# 2016_CanSat_payload_main_final.net
KiCad netlist of a schematic drawn in EAGLE
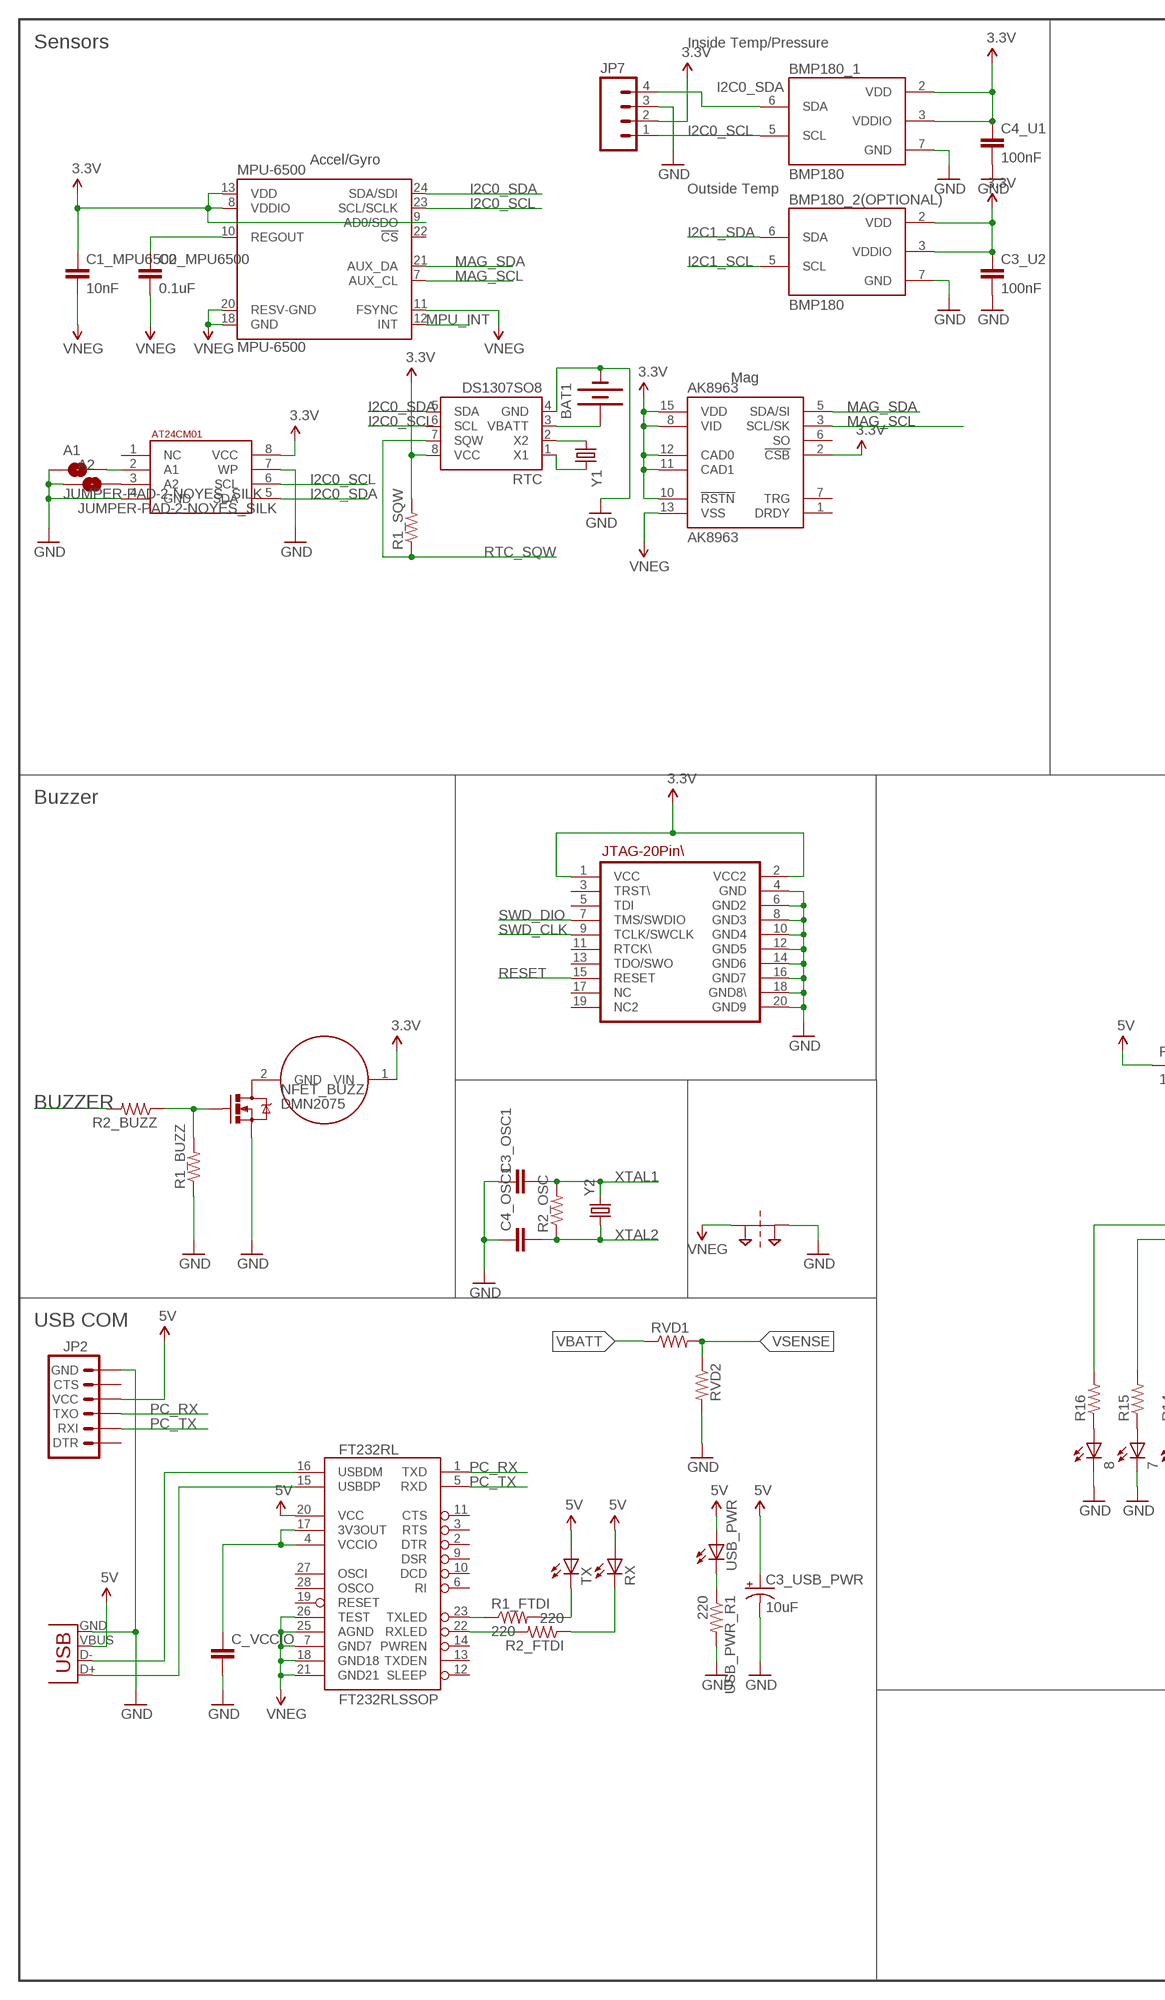
[diagram p0: schematic, sheet 1, part 1 of 2]
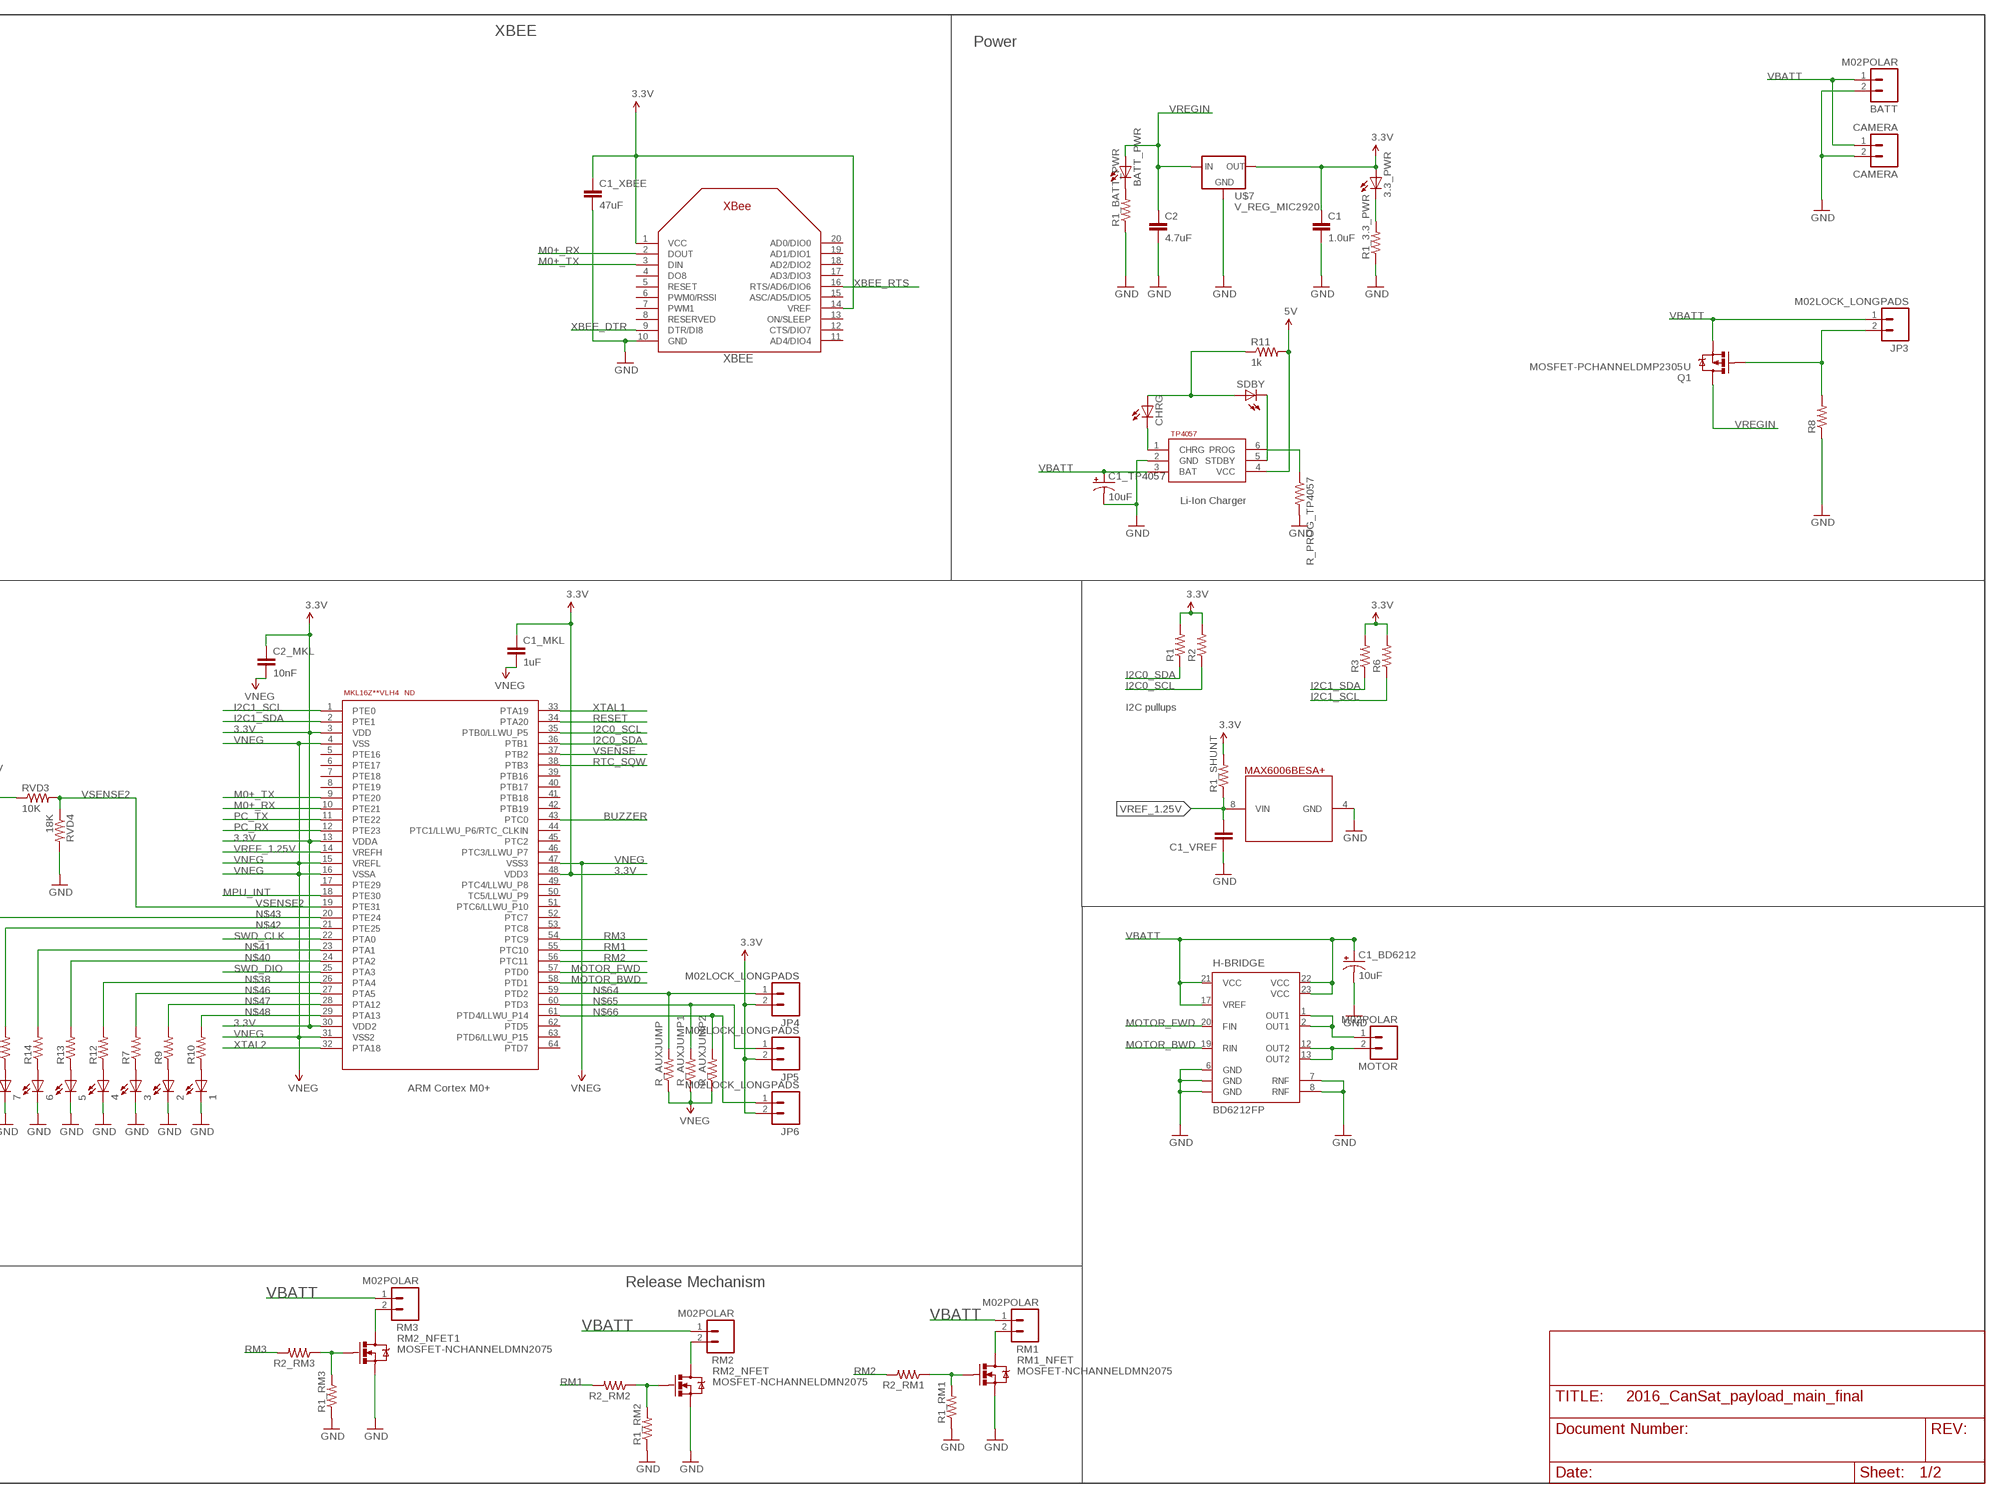
[diagram p1: schematic, sheet 1, part 2 of 2]

(export (version "E")
  (design (tool "Eeschema 10.0.6"))
  (components
    (comp (ref "1")
      (value "LEDCHIP-LED0603")
      (footprint "eagle-import:CHIP-LED0603")
      (libsource (lib "eagle-import") (part "LEDCHIP-LED0603"))
    )
    (comp (ref "2")
      (value "LEDCHIP-LED0603")
      (footprint "eagle-import:CHIP-LED0603")
      (libsource (lib "eagle-import") (part "LEDCHIP-LED0603"))
    )
    (comp (ref "3")
      (value "LEDCHIP-LED0603")
      (footprint "eagle-import:CHIP-LED0603")
      (libsource (lib "eagle-import") (part "LEDCHIP-LED0603"))
    )
    (comp (ref "3.3_PWR")
      (value "LEDCHIP-LED0603")
      (footprint "eagle-import:CHIP-LED0603")
      (libsource (lib "eagle-import") (part "LEDCHIP-LED0603"))
    )
    (comp (ref "4")
      (value "LEDCHIP-LED0603")
      (footprint "eagle-import:CHIP-LED0603")
      (libsource (lib "eagle-import") (part "LEDCHIP-LED0603"))
    )
    (comp (ref "5")
      (value "LEDCHIP-LED0603")
      (footprint "eagle-import:CHIP-LED0603")
      (libsource (lib "eagle-import") (part "LEDCHIP-LED0603"))
    )
    (comp (ref "6")
      (value "LEDCHIP-LED0603")
      (footprint "eagle-import:CHIP-LED0603")
      (libsource (lib "eagle-import") (part "LEDCHIP-LED0603"))
    )
    (comp (ref "7")
      (value "LEDCHIP-LED0603")
      (footprint "eagle-import:CHIP-LED0603")
      (libsource (lib "eagle-import") (part "LEDCHIP-LED0603"))
    )
    (comp (ref "8")
      (value "LEDCHIP-LED0603")
      (footprint "eagle-import:CHIP-LED0603")
      (libsource (lib "eagle-import") (part "LEDCHIP-LED0603"))
    )
    (comp (ref "A1")
      (value "JUMPER-PAD-2-NOYES_SILK")
      (footprint "eagle-import:PAD-JUMPER-2-NO_YES_SILK")
      (libsource (lib "eagle-import") (part "JUMPER-PAD-2-NOYES_SILK"))
    )
    (comp (ref "A2")
      (value "JUMPER-PAD-2-NOYES_SILK")
      (footprint "eagle-import:PAD-JUMPER-2-NO_YES_SILK")
      (libsource (lib "eagle-import") (part "JUMPER-PAD-2-NOYES_SILK"))
    )
    (comp (ref "AK8963")
      (value "AK8963")
      (footprint "eagle-import:QFN16-HS")
      (libsource (lib "eagle-import") (part "AK8963"))
    )
    (comp (ref "BAT1")
      (value "BATTERY12MM")
      (footprint "eagle-import:BATTCON_12MM")
      (libsource (lib "eagle-import") (part "BATTERY12MM"))
    )
    (comp (ref "BATT")
      (value "M02POLAR")
      (footprint "eagle-import:MOLEX-1X2")
      (libsource (lib "eagle-import") (part "M02POLAR"))
    )
    (comp (ref "BATT_PWR")
      (value "LEDCHIP-LED0603")
      (footprint "eagle-import:CHIP-LED0603")
      (libsource (lib "eagle-import") (part "LEDCHIP-LED0603"))
    )
    (comp (ref "BMP180_1")
      (value "BMP180")
      (footprint "eagle-import:BMP180")
      (libsource (lib "eagle-import") (part "BMP180"))
    )
    (comp (ref "BMP180_2(OPTIONAL)")
      (value "BMP180")
      (footprint "eagle-import:BMP180")
      (libsource (lib "eagle-import") (part "BMP180"))
    )
    (comp (ref "C1")
      (value "1.0uF")
      (footprint "eagle-import:0603-CAP")
      (libsource (lib "eagle-import") (part "1.0UF-16V-10%(0603)"))
    )
    (comp (ref "C1_BD6212")
      (value "10uF")
      (footprint "eagle-import:EIA3216")
      (libsource (lib "eagle-import") (part "10UF-16V-10%(TANT)"))
    )
    (comp (ref "C1_MKL")
      (value "1uF")
      (footprint "eagle-import:0603-CAP")
      (libsource (lib "eagle-import") (part "CAP0603-CAP"))
    )
    (comp (ref "C1_MPU6500")
      (value "10nF")
      (footprint "eagle-import:0603-CAP")
      (libsource (lib "eagle-import") (part "CAP0603-CAP"))
    )
    (comp (ref "C1_TP4057")
      (value "10uF")
      (footprint "eagle-import:EIA3216")
      (libsource (lib "eagle-import") (part "10UF-16V-10%(TANT)"))
    )
    (comp (ref "C1_VREF")
      (value "CAP0603-CAP")
      (footprint "eagle-import:0603-CAP")
      (libsource (lib "eagle-import") (part "SparkFun-Passives_CAP0603-CAP"))
    )
    (comp (ref "C1_XBEE")
      (value "47uF")
      (footprint "eagle-import:0603-CAP")
      (libsource (lib "eagle-import") (part "CAP0603-CAP"))
    )
    (comp (ref "C2")
      (value "4.7uF")
      (footprint "eagle-import:0603-CAP")
      (libsource (lib "eagle-import") (part "4.7UF-6.3V-10%(0603)0603"))
    )
    (comp (ref "C2_MKL")
      (value "10nF")
      (footprint "eagle-import:0603-CAP")
      (libsource (lib "eagle-import") (part "CAP0603-CAP"))
    )
    (comp (ref "C2_MPU6500")
      (value "0.1uF")
      (footprint "eagle-import:0603-CAP")
      (libsource (lib "eagle-import") (part "CAP0603-CAP"))
    )
    (comp (ref "C3_OSC1")
      (value "CAP0603-CAP")
      (footprint "eagle-import:0603-CAP")
      (libsource (lib "eagle-import") (part "SparkFun-Passives_CAP0603-CAP"))
    )
    (comp (ref "C3_U2")
      (value "100nF")
      (footprint "eagle-import:0603-CAP")
      (libsource (lib "eagle-import") (part "CAP0603-CAP"))
    )
    (comp (ref "C3_USB_PWR")
      (value "10uF")
      (footprint "eagle-import:EIA3216")
      (libsource (lib "eagle-import") (part "10UF-16V-10%(TANT)"))
    )
    (comp (ref "C4_OSC1")
      (value "CAP0603-CAP")
      (footprint "eagle-import:0603-CAP")
      (libsource (lib "eagle-import") (part "SparkFun-Passives_CAP0603-CAP"))
    )
    (comp (ref "C4_U1")
      (value "100nF")
      (footprint "eagle-import:0603-CAP")
      (libsource (lib "eagle-import") (part "CAP0603-CAP"))
    )
    (comp (ref "CAMERA")
      (value "CAMERA")
      (footprint "eagle-import:MOLEX-1X2")
      (libsource (lib "eagle-import") (part "M02POLAR"))
    )
    (comp (ref "CHRG")
      (value "LEDCHIPLED_0603")
      (footprint "eagle-import:CHIPLED_0603")
      (libsource (lib "eagle-import") (part "LEDCHIPLED_0603"))
    )
    (comp (ref "C_VCCIO")
      (value "CAP0603-CAP")
      (footprint "eagle-import:0603-CAP")
      (libsource (lib "eagle-import") (part "CAP0603-CAP"))
    )
    (comp (ref "FT232RL")
      (value "FT232RLSSOP")
      (footprint "eagle-import:SSOP28DB")
      (libsource (lib "eagle-import") (part "FT232RLSSOP"))
    )
    (comp (ref "H-BRIDGE")
      (value "BD6212FP")
      (footprint "eagle-import:HSOP25")
      (libsource (lib "eagle-import") (part "BD6212FP"))
    )
    (comp (ref "JP1")
      (value "USBOLD")
      (footprint "eagle-import:USB-MINIB-OLD")
      (libsource (lib "eagle-import") (part "USBOLD"))
    )
    (comp (ref "JP2")
      (value "ARDUINO_SERIAL_PROGRAMLONGPADS")
      (footprint "eagle-import:1X06_LONGPADS")
      (libsource (lib "eagle-import") (part "ARDUINO_SERIAL_PROGRAMLONGPADS"))
    )
    (comp (ref "JP3")
      (value "M02LOCK_LONGPADS")
      (footprint "eagle-import:1X02_LOCK_LONGPADS")
      (libsource (lib "eagle-import") (part "M02LOCK_LONGPADS"))
    )
    (comp (ref "JP4")
      (value "M02LOCK_LONGPADS")
      (footprint "eagle-import:1X02_LOCK_LONGPADS")
      (libsource (lib "eagle-import") (part "M02LOCK_LONGPADS"))
    )
    (comp (ref "JP5")
      (value "M02LOCK_LONGPADS")
      (footprint "eagle-import:1X02_LOCK_LONGPADS")
      (libsource (lib "eagle-import") (part "M02LOCK_LONGPADS"))
    )
    (comp (ref "JP6")
      (value "M02LOCK_LONGPADS")
      (footprint "eagle-import:1X02_LOCK_LONGPADS")
      (libsource (lib "eagle-import") (part "M02LOCK_LONGPADS"))
    )
    (comp (ref "JP7")
      (value "M04POLAR")
      (footprint "eagle-import:MOLEX-1X4")
      (libsource (lib "eagle-import") (part "M04POLAR"))
    )
    (comp (ref "JTAG")
      (value "JTAG_20PIN")
      (footprint "eagle-import:2X10")
      (libsource (lib "eagle-import") (part "JTAG_20PIN"))
    )
    (comp (ref "MKL16")
      (value "MKL16ZVLH4-ND")
      (footprint "eagle-import:TQFP64")
      (libsource (lib "eagle-import") (part "MKL16ZVLH4-ND"))
    )
    (comp (ref "MOTOR")
      (value "M02POLAR")
      (footprint "eagle-import:MOLEX-1X2")
      (libsource (lib "eagle-import") (part "M02POLAR"))
    )
    (comp (ref "MPU-6500")
      (value "MPU-6500")
      (footprint "eagle-import:QFN-24")
      (libsource (lib "eagle-import") (part "MPU-6500"))
    )
    (comp (ref "NFET_BUZZ")
      (value "DMN2075")
      (footprint "eagle-import:SOT23")
      (libsource (lib "eagle-import") (part "MOSFET-NCHANNELDMN2075"))
    )
    (comp (ref "PT1")
      (value "2PT_GND_TIE")
      (footprint "eagle-import:2PT_GND_TIE")
      (libsource (lib "eagle-import") (part "2PT_GND_TIE"))
    )
    (comp (ref "Q1")
      (value "MOSFET-PCHANNELDMP2305U")
      (footprint "eagle-import:SOT23-3")
      (libsource (lib "eagle-import") (part "MOSFET-PCHANNELDMP2305U"))
    )
    (comp (ref "R1")
      (value "RESISTOR0603-RES")
      (footprint "eagle-import:0603-RES")
      (libsource (lib "eagle-import") (part "RESISTOR0603-RES"))
    )
    (comp (ref "R1_3.3_PWR")
      (value "RESISTOR0603")
      (footprint "eagle-import:0603-RES")
      (libsource (lib "eagle-import") (part "RESISTOR0603"))
    )
    (comp (ref "R1_BATT_PWR")
      (value "RESISTOR0603")
      (footprint "eagle-import:0603-RES")
      (libsource (lib "eagle-import") (part "RESISTOR0603"))
    )
    (comp (ref "R1_BUZZ")
      (value "RESISTOR0805-RES")
      (footprint "eagle-import:0805")
      (libsource (lib "eagle-import") (part "SparkFun-Resistors_RESISTOR0805-RES"))
    )
    (comp (ref "R1_FTDI")
      (value "220")
      (footprint "eagle-import:0603-RES")
      (libsource (lib "eagle-import") (part "RESISTOR0603-RES"))
    )
    (comp (ref "R1_RM1")
      (value "RESISTOR0805-RES")
      (footprint "eagle-import:0805")
      (libsource (lib "eagle-import") (part "SparkFun-Resistors_RESISTOR0805-RES"))
    )
    (comp (ref "R1_RM2")
      (value "RESISTOR0805-RES")
      (footprint "eagle-import:0805")
      (libsource (lib "eagle-import") (part "SparkFun-Resistors_RESISTOR0805-RES"))
    )
    (comp (ref "R1_RM3")
      (value "RESISTOR0805-RES")
      (footprint "eagle-import:0805")
      (libsource (lib "eagle-import") (part "SparkFun-Resistors_RESISTOR0805-RES"))
    )
    (comp (ref "R1_SHUNT")
      (value "RESISTOR0805-RES")
      (footprint "eagle-import:0805")
      (libsource (lib "eagle-import") (part "SparkFun-Resistors_RESISTOR0805-RES"))
    )
    (comp (ref "R1_SQW")
      (value "RESISTOR0603-RES")
      (footprint "eagle-import:0603-RES")
      (libsource (lib "eagle-import") (part "RESISTOR0603-RES"))
    )
    (comp (ref "R2")
      (value "RESISTOR0603-RES")
      (footprint "eagle-import:0603-RES")
      (libsource (lib "eagle-import") (part "RESISTOR0603-RES"))
    )
    (comp (ref "R2_BUZZ")
      (value "RESISTOR0805-RES")
      (footprint "eagle-import:0805")
      (libsource (lib "eagle-import") (part "SparkFun-Resistors_RESISTOR0805-RES"))
    )
    (comp (ref "R2_FTDI")
      (value "220")
      (footprint "eagle-import:0603-RES")
      (libsource (lib "eagle-import") (part "RESISTOR0603-RES"))
    )
    (comp (ref "R2_OSC")
      (value "RESISTOR0805-RES")
      (footprint "eagle-import:0805")
      (libsource (lib "eagle-import") (part "SparkFun-Resistors_RESISTOR0805-RES"))
    )
    (comp (ref "R2_RM1")
      (value "RESISTOR0805-RES")
      (footprint "eagle-import:0805")
      (libsource (lib "eagle-import") (part "SparkFun-Resistors_RESISTOR0805-RES"))
    )
    (comp (ref "R2_RM2")
      (value "RESISTOR0805-RES")
      (footprint "eagle-import:0805")
      (libsource (lib "eagle-import") (part "SparkFun-Resistors_RESISTOR0805-RES"))
    )
    (comp (ref "R2_RM3")
      (value "RESISTOR0805-RES")
      (footprint "eagle-import:0805")
      (libsource (lib "eagle-import") (part "SparkFun-Resistors_RESISTOR0805-RES"))
    )
    (comp (ref "R3")
      (value "RESISTOR0603-RES")
      (footprint "eagle-import:0603-RES")
      (libsource (lib "eagle-import") (part "RESISTOR0603-RES"))
    )
    (comp (ref "R6")
      (value "RESISTOR0603-RES")
      (footprint "eagle-import:0603-RES")
      (libsource (lib "eagle-import") (part "RESISTOR0603-RES"))
    )
    (comp (ref "R7")
      (value "RESISTOR0603-RES")
      (footprint "eagle-import:0603-RES")
      (libsource (lib "eagle-import") (part "RESISTOR0603-RES"))
    )
    (comp (ref "R8")
      (value "RESISTOR0603")
      (footprint "eagle-import:0603-RES")
      (libsource (lib "eagle-import") (part "RESISTOR0603"))
    )
    (comp (ref "R9")
      (value "RESISTOR0603-RES")
      (footprint "eagle-import:0603-RES")
      (libsource (lib "eagle-import") (part "RESISTOR0603-RES"))
    )
    (comp (ref "R10")
      (value "RESISTOR0603-RES")
      (footprint "eagle-import:0603-RES")
      (libsource (lib "eagle-import") (part "RESISTOR0603-RES"))
    )
    (comp (ref "R11")
      (value "1k")
      (footprint "eagle-import:0603-RES")
      (libsource (lib "eagle-import") (part "RESISTOR0603"))
    )
    (comp (ref "R12")
      (value "RESISTOR0603-RES")
      (footprint "eagle-import:0603-RES")
      (libsource (lib "eagle-import") (part "RESISTOR0603-RES"))
    )
    (comp (ref "R13")
      (value "RESISTOR0603-RES")
      (footprint "eagle-import:0603-RES")
      (libsource (lib "eagle-import") (part "RESISTOR0603-RES"))
    )
    (comp (ref "R14")
      (value "RESISTOR0603-RES")
      (footprint "eagle-import:0603-RES")
      (libsource (lib "eagle-import") (part "RESISTOR0603-RES"))
    )
    (comp (ref "R15")
      (value "RESISTOR0603-RES")
      (footprint "eagle-import:0603-RES")
      (libsource (lib "eagle-import") (part "RESISTOR0603-RES"))
    )
    (comp (ref "R16")
      (value "RESISTOR0603-RES")
      (footprint "eagle-import:0603-RES")
      (libsource (lib "eagle-import") (part "RESISTOR0603-RES"))
    )
    (comp (ref "RM1")
      (value "M02POLAR")
      (footprint "eagle-import:MOLEX-1X2")
      (libsource (lib "eagle-import") (part "M02POLAR"))
    )
    (comp (ref "RM1_NFET")
      (value "MOSFET-NCHANNELDMN2075")
      (footprint "eagle-import:SOT23")
      (libsource (lib "eagle-import") (part "MOSFET-NCHANNELDMN2075"))
    )
    (comp (ref "RM2")
      (value "M02POLAR")
      (footprint "eagle-import:MOLEX-1X2")
      (libsource (lib "eagle-import") (part "M02POLAR"))
    )
    (comp (ref "RM2_NFET")
      (value "MOSFET-NCHANNELDMN2075")
      (footprint "eagle-import:SOT23")
      (libsource (lib "eagle-import") (part "MOSFET-NCHANNELDMN2075"))
    )
    (comp (ref "RM2_NFET1")
      (value "MOSFET-NCHANNELDMN2075")
      (footprint "eagle-import:SOT23")
      (libsource (lib "eagle-import") (part "MOSFET-NCHANNELDMN2075"))
    )
    (comp (ref "RM3")
      (value "M02POLAR")
      (footprint "eagle-import:MOLEX-1X2")
      (libsource (lib "eagle-import") (part "M02POLAR"))
    )
    (comp (ref "RTC")
      (value "DS1307SO8")
      (footprint "eagle-import:SO08")
      (libsource (lib "eagle-import") (part "DS1307SO8"))
    )
    (comp (ref "RVD1")
      (value "RESISTOR0805-RES")
      (footprint "eagle-import:0805")
      (libsource (lib "eagle-import") (part "SparkFun-Resistors_RESISTOR0805-RES"))
    )
    (comp (ref "RVD2")
      (value "RESISTOR0805-RES")
      (footprint "eagle-import:0805")
      (libsource (lib "eagle-import") (part "SparkFun-Resistors_RESISTOR0805-RES"))
    )
    (comp (ref "RVD3")
      (value "10K")
      (footprint "eagle-import:0805")
      (libsource (lib "eagle-import") (part "SparkFun-Resistors_RESISTOR0805-RES"))
    )
    (comp (ref "RVD4")
      (value "18K")
      (footprint "eagle-import:0805")
      (libsource (lib "eagle-import") (part "SparkFun-Resistors_RESISTOR0805-RES"))
    )
    (comp (ref "RX")
      (value "LEDCHIPLED_0603")
      (footprint "eagle-import:CHIPLED_0603")
      (libsource (lib "eagle-import") (part "LEDCHIPLED_0603"))
    )
    (comp (ref "R_AUXJUMP")
      (value "RESISTOR0805-RES")
      (footprint "eagle-import:0805")
      (libsource (lib "eagle-import") (part "SparkFun-Resistors_RESISTOR0805-RES"))
    )
    (comp (ref "R_AUXJUMP1")
      (value "RESISTOR0805-RES")
      (footprint "eagle-import:0805")
      (libsource (lib "eagle-import") (part "SparkFun-Resistors_RESISTOR0805-RES"))
    )
    (comp (ref "R_AUXJUMP2")
      (value "RESISTOR0805-RES")
      (footprint "eagle-import:0805")
      (libsource (lib "eagle-import") (part "SparkFun-Resistors_RESISTOR0805-RES"))
    )
    (comp (ref "R_PROG_TP4057")
      (value "RESISTOR0603")
      (footprint "eagle-import:0603-RES")
      (libsource (lib "eagle-import") (part "RESISTOR0603"))
    )
    (comp (ref "SDBY")
      (value "LEDCHIPLED_0603")
      (footprint "eagle-import:CHIPLED_0603")
      (libsource (lib "eagle-import") (part "LEDCHIPLED_0603"))
    )
    (comp (ref "TX")
      (value "LEDCHIPLED_0603")
      (footprint "eagle-import:CHIPLED_0603")
      (libsource (lib "eagle-import") (part "LEDCHIPLED_0603"))
    )
    (comp (ref "U$2")
      (value "AT24CM01")
      (footprint "eagle-import:SO08")
      (libsource (lib "eagle-import") (part "AT24CM01"))
    )
    (comp (ref "U$3")
      (value "TP4057")
      (footprint "eagle-import:SOT23-6")
      (libsource (lib "eagle-import") (part "TP4057"))
    )
    (comp (ref "U$4")
      (value "AI-1027-TWT-3V-R_BUZZER")
      (footprint "eagle-import:AI-1027-TWT-3V-R_BUZZER")
      (libsource (lib "eagle-import") (part "AI-1027-TWT-3V-R_BUZZER"))
    )
    (comp (ref "U$5")
      (value "MAX6006BESA+")
      (footprint "eagle-import:SO08")
      (libsource (lib "eagle-import") (part "MAX6006BESA+"))
    )
    (comp (ref "U$7")
      (value "V_REG_MIC2920")
      (footprint "eagle-import:SOT223")
      (libsource (lib "eagle-import") (part "V_REG_MIC2920"))
    )
    (comp (ref "USB_PWR")
      (value "LEDCHIPLED_0603")
      (footprint "eagle-import:CHIPLED_0603")
      (libsource (lib "eagle-import") (part "LEDCHIPLED_0603"))
    )
    (comp (ref "USB_PWR_R1")
      (value "220")
      (footprint "eagle-import:0603-RES")
      (libsource (lib "eagle-import") (part "RESISTOR0603-RES"))
    )
    (comp (ref "XBEE")
      (value "XBEE")
      (footprint "eagle-import:XBEE")
      (libsource (lib "eagle-import") (part "XBEE"))
    )
    (comp (ref "Y1")
      (value "CRYSTAL32-SMD")
      (footprint "eagle-import:CRYSTAL-32KHZ-SMD")
      (libsource (lib "eagle-import") (part "CRYSTAL32-SMD"))
    )
    (comp (ref "Y2")
      (value "CRYSTAL5X3")
      (footprint "eagle-import:CRYSTAL-SMD-5X3")
      (libsource (lib "eagle-import") (part "CRYSTAL5X3"))
    )
  )
  (nets
    (net (code "1") (name "3.3V") (class "Default")
      (node (ref "3.3_PWR") (pin "A") (pinfunction "A_A") (pintype "passive"))
      (node (ref "AK8963") (pin "10") (pinfunction "~{RSTN}_10") (pintype "input"))
      (node (ref "AK8963") (pin "11") (pinfunction "CAD1_11") (pintype "input"))
      (node (ref "AK8963") (pin "12") (pinfunction "CAD0_12") (pintype "input"))
      (node (ref "AK8963") (pin "15") (pinfunction "VDD_15") (pintype "power_in"))
      (node (ref "AK8963") (pin "2") (pinfunction "~{CSB}_2") (pintype "input"))
      (node (ref "AK8963") (pin "8") (pinfunction "VID_8") (pintype "power_in"))
      (node (ref "BMP180_1") (pin "2") (pinfunction "VDD_2") (pintype "power_in"))
      (node (ref "BMP180_1") (pin "3") (pinfunction "VDDIO_3") (pintype "power_in"))
      (node (ref "BMP180_2(OPTIONAL)") (pin "2") (pinfunction "VDD_2") (pintype "power_in"))
      (node (ref "BMP180_2(OPTIONAL)") (pin "3") (pinfunction "VDDIO_3") (pintype "power_in"))
      (node (ref "C1") (pin "1") (pinfunction "1_1") (pintype "passive"))
      (node (ref "C1_MKL") (pin "1") (pinfunction "1_1") (pintype "passive"))
      (node (ref "C1_MPU6500") (pin "1") (pinfunction "1_1") (pintype "passive"))
      (node (ref "C1_XBEE") (pin "1") (pinfunction "1_1") (pintype "passive"))
      (node (ref "C2_MKL") (pin "1") (pinfunction "1_1") (pintype "passive"))
      (node (ref "C3_U2") (pin "1") (pinfunction "1_1") (pintype "passive"))
      (node (ref "C4_U1") (pin "1") (pinfunction "1_1") (pintype "passive"))
      (node (ref "JP4") (pin "2") (pinfunction "2_2") (pintype "passive"))
      (node (ref "JP5") (pin "2") (pinfunction "2_2") (pintype "passive"))
      (node (ref "JP6") (pin "2") (pinfunction "2_2") (pintype "passive"))
      (node (ref "JP7") (pin "2") (pinfunction "2_2") (pintype "passive"))
      (node (ref "JTAG") (pin "1") (pinfunction "VCC_1") (pintype "bidirectional"))
      (node (ref "JTAG") (pin "2") (pinfunction "VCC2_2") (pintype "bidirectional"))
      (node (ref "MKL16") (pin "13") (pinfunction "VDDA_13") (pintype "bidirectional"))
      (node (ref "MKL16") (pin "3") (pinfunction "VDD_3") (pintype "bidirectional"))
      (node (ref "MKL16") (pin "30") (pinfunction "VDD2_30") (pintype "bidirectional"))
      (node (ref "MKL16") (pin "48") (pinfunction "VDD3_48") (pintype "bidirectional"))
      (node (ref "MPU-6500") (pin "13") (pinfunction "VDD_13") (pintype "bidirectional"))
      (node (ref "MPU-6500") (pin "8") (pinfunction "VDDIO_8") (pintype "bidirectional"))
      (node (ref "MPU-6500") (pin "9") (pinfunction "AD0/SDO_9") (pintype "bidirectional"))
      (node (ref "R1") (pin "2") (pinfunction "2_2") (pintype "passive"))
      (node (ref "R1_SHUNT") (pin "2") (pinfunction "2_2") (pintype "passive"))
      (node (ref "R1_SQW") (pin "2") (pinfunction "2_2") (pintype "passive"))
      (node (ref "R2") (pin "2") (pinfunction "2_2") (pintype "passive"))
      (node (ref "R3") (pin "2") (pinfunction "2_2") (pintype "passive"))
      (node (ref "R6") (pin "2") (pinfunction "2_2") (pintype "passive"))
      (node (ref "RTC") (pin "8") (pinfunction "VCC_8") (pintype "bidirectional"))
      (node (ref "U$2") (pin "8") (pinfunction "VCC_8") (pintype "power_in"))
      (node (ref "U$4") (pin "1") (pinfunction "VIN_1") (pintype "bidirectional"))
      (node (ref "U$7") (pin "3") (pinfunction "OUT_3") (pintype "output"))
      (node (ref "XBEE") (pin "1") (pinfunction "VCC_1") (pintype "power_in"))
      (node (ref "XBEE") (pin "14") (pinfunction "VREF_14") (pintype "input"))
    )
    (net (code "2") (name "5V") (class "Default")
      (node (ref "C3_USB_PWR") (pin "A") (pinfunction "+_A") (pintype "passive"))
      (node (ref "FT232RL") (pin "20") (pinfunction "VCC_20") (pintype "power_in"))
      (node (ref "JP1") (pin "VBUS") (pinfunction "VBUS_VBUS") (pintype "bidirectional"))
      (node (ref "JP2") (pin "4") (pinfunction "VCC_4") (pintype "passive"))
      (node (ref "R11") (pin "2") (pinfunction "2_2") (pintype "passive"))
      (node (ref "RVD3") (pin "1") (pinfunction "1_1") (pintype "passive"))
      (node (ref "RX") (pin "A") (pinfunction "A_A") (pintype "passive"))
      (node (ref "TX") (pin "A") (pinfunction "A_A") (pintype "passive"))
      (node (ref "U$3") (pin "4") (pinfunction "VCC_4") (pintype "bidirectional"))
      (node (ref "USB_PWR") (pin "A") (pinfunction "A_A") (pintype "passive"))
    )
    (net (code "3") (name "BUZZER") (class "Default")
      (node (ref "MKL16") (pin "43") (pinfunction "PTC0_43") (pintype "bidirectional"))
      (node (ref "R2_BUZZ") (pin "2") (pinfunction "2_2") (pintype "passive"))
    )
    (net (code "4") (name "GND") (class "Default")
      (node (ref "1") (pin "C") (pinfunction "C_C") (pintype "passive"))
      (node (ref "2") (pin "C") (pinfunction "C_C") (pintype "passive"))
      (node (ref "3") (pin "C") (pinfunction "C_C") (pintype "passive"))
      (node (ref "4") (pin "C") (pinfunction "C_C") (pintype "passive"))
      (node (ref "5") (pin "C") (pinfunction "C_C") (pintype "passive"))
      (node (ref "6") (pin "C") (pinfunction "C_C") (pintype "passive"))
      (node (ref "7") (pin "C") (pinfunction "C_C") (pintype "passive"))
      (node (ref "8") (pin "C") (pinfunction "C_C") (pintype "passive"))
      (node (ref "A1") (pin "1") (pinfunction "1_1") (pintype "passive"))
      (node (ref "A2") (pin "1") (pinfunction "1_1") (pintype "passive"))
      (node (ref "BAT1") (pin "GND") (pinfunction "-_GND") (pintype "power_in"))
      (node (ref "BATT") (pin "2") (pinfunction "2_2") (pintype "passive"))
      (node (ref "BMP180_1") (pin "7") (pinfunction "GND_7") (pintype "power_in"))
      (node (ref "BMP180_2(OPTIONAL)") (pin "7") (pinfunction "GND_7") (pintype "power_in"))
      (node (ref "C1") (pin "2") (pinfunction "2_2") (pintype "passive"))
      (node (ref "C1_BD6212") (pin "C") (pinfunction "-_C") (pintype "passive"))
      (node (ref "C1_TP4057") (pin "C") (pinfunction "-_C") (pintype "passive"))
      (node (ref "C1_VREF") (pin "1") (pinfunction "1_1") (pintype "passive"))
      (node (ref "C1_XBEE") (pin "2") (pinfunction "2_2") (pintype "passive"))
      (node (ref "C2") (pin "2") (pinfunction "2_2") (pintype "passive"))
      (node (ref "C3_OSC1") (pin "1") (pinfunction "1_1") (pintype "passive"))
      (node (ref "C3_U2") (pin "2") (pinfunction "2_2") (pintype "passive"))
      (node (ref "C3_USB_PWR") (pin "C") (pinfunction "-_C") (pintype "passive"))
      (node (ref "C4_OSC1") (pin "1") (pinfunction "1_1") (pintype "passive"))
      (node (ref "C4_U1") (pin "2") (pinfunction "2_2") (pintype "passive"))
      (node (ref "CAMERA") (pin "2") (pinfunction "2_2") (pintype "passive"))
      (node (ref "C_VCCIO") (pin "2") (pinfunction "2_2") (pintype "passive"))
      (node (ref "H-BRIDGE") (pin "6") (pinfunction "GND_6") (pintype "power_in"))
      (node (ref "H-BRIDGE") (pin "7") (pinfunction "RNF_7") (pintype "bidirectional"))
      (node (ref "H-BRIDGE") (pin "8") (pinfunction "RNF_8") (pintype "bidirectional"))
      (node (ref "H-BRIDGE") (pin "GND@1") (pinfunction "GND_GND@1") (pintype "power_in"))
      (node (ref "H-BRIDGE") (pin "GND@2") (pinfunction "GND_GND@2") (pintype "power_in"))
      (node (ref "JP1") (pin "GND") (pinfunction "GND_GND") (pintype "bidirectional"))
      (node (ref "JP2") (pin "6") (pinfunction "GND_6") (pintype "passive"))
      (node (ref "JP7") (pin "3") (pinfunction "3_3") (pintype "passive"))
      (node (ref "JTAG") (pin "10") (pinfunction "GND4_10") (pintype "bidirectional"))
      (node (ref "JTAG") (pin "12") (pinfunction "GND5_12") (pintype "bidirectional"))
      (node (ref "JTAG") (pin "14") (pinfunction "GND6_14") (pintype "bidirectional"))
      (node (ref "JTAG") (pin "16") (pinfunction "GND7_16") (pintype "bidirectional"))
      (node (ref "JTAG") (pin "18") (pinfunction "GND8\\_18") (pintype "bidirectional"))
      (node (ref "JTAG") (pin "20") (pinfunction "GND9_20") (pintype "bidirectional"))
      (node (ref "JTAG") (pin "4") (pinfunction "GND_4") (pintype "bidirectional"))
      (node (ref "JTAG") (pin "6") (pinfunction "GND2_6") (pintype "bidirectional"))
      (node (ref "JTAG") (pin "8") (pinfunction "GND3_8") (pintype "bidirectional"))
      (node (ref "NFET_BUZZ") (pin "2") (pinfunction "S_2") (pintype "passive"))
      (node (ref "PT1") (pin "P$2") (pinfunction "P$2_P$2") (pintype "bidirectional"))
      (node (ref "R1_3.3_PWR") (pin "1") (pinfunction "1_1") (pintype "passive"))
      (node (ref "R1_BATT_PWR") (pin "1") (pinfunction "1_1") (pintype "passive"))
      (node (ref "R1_BUZZ") (pin "1") (pinfunction "1_1") (pintype "passive"))
      (node (ref "R1_RM1") (pin "1") (pinfunction "1_1") (pintype "passive"))
      (node (ref "R1_RM2") (pin "1") (pinfunction "1_1") (pintype "passive"))
      (node (ref "R1_RM3") (pin "1") (pinfunction "1_1") (pintype "passive"))
      (node (ref "R8") (pin "1") (pinfunction "1_1") (pintype "passive"))
      (node (ref "RM1_NFET") (pin "2") (pinfunction "S_2") (pintype "passive"))
      (node (ref "RM2_NFET") (pin "2") (pinfunction "S_2") (pintype "passive"))
      (node (ref "RM2_NFET1") (pin "2") (pinfunction "S_2") (pintype "passive"))
      (node (ref "RTC") (pin "4") (pinfunction "GND_4") (pintype "bidirectional"))
      (node (ref "RVD2") (pin "2") (pinfunction "2_2") (pintype "passive"))
      (node (ref "RVD4") (pin "2") (pinfunction "2_2") (pintype "passive"))
      (node (ref "R_PROG_TP4057") (pin "2") (pinfunction "2_2") (pintype "passive"))
      (node (ref "U$2") (pin "4") (pinfunction "GND_4") (pintype "power_in"))
      (node (ref "U$2") (pin "7") (pinfunction "WP_7") (pintype "bidirectional"))
      (node (ref "U$3") (pin "2") (pinfunction "GND_2") (pintype "bidirectional"))
      (node (ref "U$5") (pin "4") (pinfunction "GND_4") (pintype "bidirectional"))
      (node (ref "U$7") (pin "2") (pinfunction "GND_2") (pintype "input"))
      (node (ref "USB_PWR_R1") (pin "2") (pinfunction "2_2") (pintype "passive"))
      (node (ref "XBEE") (pin "10") (pinfunction "GND_10") (pintype "power_in"))
    )
    (net (code "5") (name "I2C0_SCL") (class "Default")
      (node (ref "BMP180_1") (pin "5") (pinfunction "SCL_5") (pintype "input"))
      (node (ref "JP7") (pin "1") (pinfunction "1_1") (pintype "passive"))
      (node (ref "MKL16") (pin "35") (pinfunction "PTB0/LLWU_P5_35") (pintype "bidirectional"))
      (node (ref "MPU-6500") (pin "23") (pinfunction "SCL/SCLK_23") (pintype "bidirectional"))
      (node (ref "R2") (pin "1") (pinfunction "1_1") (pintype "passive"))
      (node (ref "RTC") (pin "6") (pinfunction "SCL_6") (pintype "bidirectional"))
      (node (ref "U$2") (pin "6") (pinfunction "SCL_6") (pintype "bidirectional"))
    )
    (net (code "6") (name "I2C0_SDA") (class "Default")
      (node (ref "BMP180_1") (pin "6") (pinfunction "SDA_6") (pintype "bidirectional"))
      (node (ref "JP7") (pin "4") (pinfunction "4_4") (pintype "passive"))
      (node (ref "MKL16") (pin "36") (pinfunction "PTB1_36") (pintype "bidirectional"))
      (node (ref "MPU-6500") (pin "24") (pinfunction "SDA/SDI_24") (pintype "bidirectional"))
      (node (ref "R1") (pin "1") (pinfunction "1_1") (pintype "passive"))
      (node (ref "RTC") (pin "5") (pinfunction "SDA_5") (pintype "bidirectional"))
      (node (ref "U$2") (pin "5") (pinfunction "SDA_5") (pintype "bidirectional"))
    )
    (net (code "7") (name "I2C1_SCL") (class "Default")
      (node (ref "BMP180_2(OPTIONAL)") (pin "5") (pinfunction "SCL_5") (pintype "input"))
      (node (ref "MKL16") (pin "1") (pinfunction "PTE0_1") (pintype "bidirectional"))
      (node (ref "R6") (pin "1") (pinfunction "1_1") (pintype "passive"))
    )
    (net (code "8") (name "I2C1_SDA") (class "Default")
      (node (ref "BMP180_2(OPTIONAL)") (pin "6") (pinfunction "SDA_6") (pintype "bidirectional"))
      (node (ref "MKL16") (pin "2") (pinfunction "PTE1_2") (pintype "bidirectional"))
      (node (ref "R3") (pin "1") (pinfunction "1_1") (pintype "passive"))
    )
    (net (code "9") (name "M0+_RX") (class "Default")
      (node (ref "MKL16") (pin "10") (pinfunction "PTE21_10") (pintype "bidirectional"))
      (node (ref "XBEE") (pin "2") (pinfunction "DOUT_2") (pintype "output"))
    )
    (net (code "10") (name "M0+_TX") (class "Default")
      (node (ref "MKL16") (pin "9") (pinfunction "PTE20_9") (pintype "bidirectional"))
      (node (ref "XBEE") (pin "3") (pinfunction "DIN_3") (pintype "input"))
    )
    (net (code "11") (name "MAG_SCL") (class "Default")
      (node (ref "AK8963") (pin "3") (pinfunction "SCL/SK_3") (pintype "input"))
      (node (ref "MPU-6500") (pin "7") (pinfunction "AUX_CL_7") (pintype "bidirectional"))
    )
    (net (code "12") (name "MAG_SDA") (class "Default")
      (node (ref "AK8963") (pin "5") (pinfunction "SDA/SI_5") (pintype "bidirectional"))
      (node (ref "MPU-6500") (pin "21") (pinfunction "AUX_DA_21") (pintype "bidirectional"))
    )
    (net (code "13") (name "MOTOR_BWD") (class "Default")
      (node (ref "H-BRIDGE") (pin "19") (pinfunction "RIN_19") (pintype "input"))
      (node (ref "MKL16") (pin "58") (pinfunction "PTD1_58") (pintype "bidirectional"))
    )
    (net (code "14") (name "MOTOR_FWD") (class "Default")
      (node (ref "H-BRIDGE") (pin "20") (pinfunction "FIN_20") (pintype "input"))
      (node (ref "MKL16") (pin "57") (pinfunction "PTD0_57") (pintype "bidirectional"))
    )
    (net (code "15") (name "MPU_INT") (class "Default")
      (node (ref "MKL16") (pin "18") (pinfunction "PTE30_18") (pintype "bidirectional"))
      (node (ref "MPU-6500") (pin "12") (pinfunction "INT_12") (pintype "bidirectional"))
    )
    (net (code "16") (name "N$38") (class "Default")
      (node (ref "MKL16") (pin "26") (pinfunction "PTA4_26") (pintype "bidirectional"))
      (node (ref "R12") (pin "2") (pinfunction "2_2") (pintype "passive"))
    )
    (net (code "17") (name "N$40") (class "Default")
      (node (ref "MKL16") (pin "24") (pinfunction "PTA2_24") (pintype "bidirectional"))
      (node (ref "R13") (pin "2") (pinfunction "2_2") (pintype "passive"))
    )
    (net (code "18") (name "N$41") (class "Default")
      (node (ref "MKL16") (pin "23") (pinfunction "PTA1_23") (pintype "bidirectional"))
      (node (ref "R14") (pin "2") (pinfunction "2_2") (pintype "passive"))
    )
    (net (code "19") (name "N$42") (class "Default")
      (node (ref "MKL16") (pin "21") (pinfunction "PTE25_21") (pintype "bidirectional"))
      (node (ref "R15") (pin "2") (pinfunction "2_2") (pintype "passive"))
    )
    (net (code "20") (name "N$43") (class "Default")
      (node (ref "MKL16") (pin "20") (pinfunction "PTE24_20") (pintype "bidirectional"))
      (node (ref "R16") (pin "2") (pinfunction "2_2") (pintype "passive"))
    )
    (net (code "21") (name "N$46") (class "Default")
      (node (ref "MKL16") (pin "27") (pinfunction "PTA5_27") (pintype "bidirectional"))
      (node (ref "R7") (pin "2") (pinfunction "2_2") (pintype "passive"))
    )
    (net (code "22") (name "N$47") (class "Default")
      (node (ref "MKL16") (pin "28") (pinfunction "PTA12_28") (pintype "bidirectional"))
      (node (ref "R9") (pin "2") (pinfunction "2_2") (pintype "passive"))
    )
    (net (code "23") (name "N$48") (class "Default")
      (node (ref "MKL16") (pin "29") (pinfunction "PTA13_29") (pintype "bidirectional"))
      (node (ref "R10") (pin "2") (pinfunction "2_2") (pintype "passive"))
    )
    (net (code "24") (name "N$64") (class "Default")
      (node (ref "JP4") (pin "1") (pinfunction "1_1") (pintype "passive"))
      (node (ref "MKL16") (pin "59") (pinfunction "PTD2_59") (pintype "bidirectional"))
      (node (ref "R_AUXJUMP") (pin "2") (pinfunction "2_2") (pintype "passive"))
    )
    (net (code "25") (name "N$65") (class "Default")
      (node (ref "JP5") (pin "1") (pinfunction "1_1") (pintype "passive"))
      (node (ref "MKL16") (pin "60") (pinfunction "PTD3_60") (pintype "bidirectional"))
      (node (ref "R_AUXJUMP1") (pin "2") (pinfunction "2_2") (pintype "passive"))
    )
    (net (code "26") (name "N$66") (class "Default")
      (node (ref "JP6") (pin "1") (pinfunction "1_1") (pintype "passive"))
      (node (ref "MKL16") (pin "61") (pinfunction "PTD4/LLWU_P14_61") (pintype "bidirectional"))
      (node (ref "R_AUXJUMP2") (pin "2") (pinfunction "2_2") (pintype "passive"))
    )
    (net (code "27") (name "Net-(1-PadA)") (class "Default")
      (node (ref "1") (pin "A") (pinfunction "A_A") (pintype "passive"))
      (node (ref "R10") (pin "1") (pinfunction "1_1") (pintype "passive"))
    )
    (net (code "28") (name "Net-(2-PadA)") (class "Default")
      (node (ref "2") (pin "A") (pinfunction "A_A") (pintype "passive"))
      (node (ref "R9") (pin "1") (pinfunction "1_1") (pintype "passive"))
    )
    (net (code "29") (name "Net-(3-PadA)") (class "Default")
      (node (ref "3") (pin "A") (pinfunction "A_A") (pintype "passive"))
      (node (ref "R7") (pin "1") (pinfunction "1_1") (pintype "passive"))
    )
    (net (code "30") (name "Net-(3.3_PWR-PadC)") (class "Default")
      (node (ref "3.3_PWR") (pin "C") (pinfunction "C_C") (pintype "passive"))
      (node (ref "R1_3.3_PWR") (pin "2") (pinfunction "2_2") (pintype "passive"))
    )
    (net (code "31") (name "Net-(4-PadA)") (class "Default")
      (node (ref "4") (pin "A") (pinfunction "A_A") (pintype "passive"))
      (node (ref "R12") (pin "1") (pinfunction "1_1") (pintype "passive"))
    )
    (net (code "32") (name "Net-(5-PadA)") (class "Default")
      (node (ref "5") (pin "A") (pinfunction "A_A") (pintype "passive"))
      (node (ref "R13") (pin "1") (pinfunction "1_1") (pintype "passive"))
    )
    (net (code "33") (name "Net-(6-PadA)") (class "Default")
      (node (ref "6") (pin "A") (pinfunction "A_A") (pintype "passive"))
      (node (ref "R14") (pin "1") (pinfunction "1_1") (pintype "passive"))
    )
    (net (code "34") (name "Net-(7-PadA)") (class "Default")
      (node (ref "7") (pin "A") (pinfunction "A_A") (pintype "passive"))
      (node (ref "R15") (pin "1") (pinfunction "1_1") (pintype "passive"))
    )
    (net (code "35") (name "Net-(8-PadA)") (class "Default")
      (node (ref "8") (pin "A") (pinfunction "A_A") (pintype "passive"))
      (node (ref "R16") (pin "1") (pinfunction "1_1") (pintype "passive"))
    )
    (net (code "36") (name "Net-(BAT1-+)") (class "Default")
      (node (ref "BAT1") (pin "PWR@1") (pinfunction "+_PWR@1") (pintype "power_in"))
      (node (ref "RTC") (pin "3") (pinfunction "VBATT_3") (pintype "bidirectional"))
    )
    (net (code "37") (name "Net-(BATT_PWR-PadC)") (class "Default")
      (node (ref "BATT_PWR") (pin "C") (pinfunction "C_C") (pintype "passive"))
      (node (ref "R1_BATT_PWR") (pin "2") (pinfunction "2_2") (pintype "passive"))
    )
    (net (code "38") (name "Net-(CHRG-PadA)") (class "Default")
      (node (ref "CHRG") (pin "A") (pinfunction "A_A") (pintype "passive"))
      (node (ref "R11") (pin "1") (pinfunction "1_1") (pintype "passive"))
      (node (ref "SDBY") (pin "A") (pinfunction "A_A") (pintype "passive"))
    )
    (net (code "39") (name "Net-(FT232RL-3V3OUT)") (class "Default")
      (node (ref "C_VCCIO") (pin "1") (pinfunction "1_1") (pintype "passive"))
      (node (ref "FT232RL") (pin "17") (pinfunction "3V3OUT_17") (pintype "output"))
      (node (ref "FT232RL") (pin "4") (pinfunction "VCCIO_4") (pintype "power_in"))
    )
    (net (code "40") (name "Net-(FT232RL-RXLED)") (class "Default")
      (node (ref "FT232RL") (pin "22") (pinfunction "RXLED_22") (pintype "input"))
      (node (ref "R2_FTDI") (pin "2") (pinfunction "2_2") (pintype "passive"))
    )
    (net (code "41") (name "Net-(FT232RL-TXLED)") (class "Default")
      (node (ref "FT232RL") (pin "23") (pinfunction "TXLED_23") (pintype "input"))
      (node (ref "R1_FTDI") (pin "1") (pinfunction "1_1") (pintype "passive"))
    )
    (net (code "42") (name "Net-(FT232RL-USBDM)") (class "Default")
      (node (ref "FT232RL") (pin "16") (pinfunction "USBDM_16") (pintype "bidirectional"))
      (node (ref "JP1") (pin "D-") (pinfunction "D-_D-") (pintype "bidirectional"))
    )
    (net (code "43") (name "Net-(FT232RL-USBDP)") (class "Default")
      (node (ref "FT232RL") (pin "15") (pinfunction "USBDP_15") (pintype "bidirectional"))
      (node (ref "JP1") (pin "D+") (pinfunction "D+_D+") (pintype "bidirectional"))
    )
    (net (code "44") (name "Net-(H-BRIDGE-OUT1-Pad1)") (class "Default")
      (node (ref "H-BRIDGE") (pin "1") (pinfunction "OUT1_1") (pintype "output"))
      (node (ref "H-BRIDGE") (pin "2") (pinfunction "OUT1_2") (pintype "output"))
      (node (ref "MOTOR") (pin "1") (pinfunction "1_1") (pintype "passive"))
    )
    (net (code "45") (name "Net-(H-BRIDGE-OUT2-Pad12)") (class "Default")
      (node (ref "H-BRIDGE") (pin "12") (pinfunction "OUT2_12") (pintype "output"))
      (node (ref "H-BRIDGE") (pin "13") (pinfunction "OUT2_13") (pintype "output"))
      (node (ref "MOTOR") (pin "2") (pinfunction "2_2") (pintype "passive"))
    )
    (net (code "46") (name "Net-(MPU-6500-REGOUT)") (class "Default")
      (node (ref "C2_MPU6500") (pin "1") (pinfunction "1_1") (pintype "passive"))
      (node (ref "MPU-6500") (pin "10") (pinfunction "REGOUT_10") (pintype "bidirectional"))
    )
    (net (code "47") (name "Net-(NFET_BUZZ-D)") (class "Default")
      (node (ref "NFET_BUZZ") (pin "3") (pinfunction "D_3") (pintype "passive"))
      (node (ref "U$4") (pin "2") (pinfunction "GND_2") (pintype "bidirectional"))
    )
    (net (code "48") (name "Net-(NFET_BUZZ-G)") (class "Default")
      (node (ref "NFET_BUZZ") (pin "1") (pinfunction "G_1") (pintype "passive"))
      (node (ref "R1_BUZZ") (pin "2") (pinfunction "2_2") (pintype "passive"))
      (node (ref "R2_BUZZ") (pin "1") (pinfunction "1_1") (pintype "passive"))
    )
    (net (code "49") (name "Net-(Q1-G)") (class "Default")
      (node (ref "JP3") (pin "2") (pinfunction "2_2") (pintype "passive"))
      (node (ref "Q1") (pin "1") (pinfunction "G_1") (pintype "passive"))
      (node (ref "R8") (pin "2") (pinfunction "2_2") (pintype "passive"))
    )
    (net (code "50") (name "Net-(R1_FTDI-Pad2)") (class "Default")
      (node (ref "R1_FTDI") (pin "2") (pinfunction "2_2") (pintype "passive"))
      (node (ref "TX") (pin "C") (pinfunction "C_C") (pintype "passive"))
    )
    (net (code "51") (name "Net-(R2_FTDI-Pad1)") (class "Default")
      (node (ref "R2_FTDI") (pin "1") (pinfunction "1_1") (pintype "passive"))
      (node (ref "RX") (pin "C") (pinfunction "C_C") (pintype "passive"))
    )
    (net (code "52") (name "Net-(RM1_NFET-D)") (class "Default")
      (node (ref "RM1") (pin "2") (pinfunction "2_2") (pintype "passive"))
      (node (ref "RM1_NFET") (pin "3") (pinfunction "D_3") (pintype "passive"))
    )
    (net (code "53") (name "Net-(RM1_NFET-G)") (class "Default")
      (node (ref "R1_RM1") (pin "2") (pinfunction "2_2") (pintype "passive"))
      (node (ref "R2_RM1") (pin "1") (pinfunction "1_1") (pintype "passive"))
      (node (ref "RM1_NFET") (pin "1") (pinfunction "G_1") (pintype "passive"))
    )
    (net (code "54") (name "Net-(RM2_NFET-D)") (class "Default")
      (node (ref "RM2") (pin "2") (pinfunction "2_2") (pintype "passive"))
      (node (ref "RM2_NFET") (pin "3") (pinfunction "D_3") (pintype "passive"))
    )
    (net (code "55") (name "Net-(RM2_NFET-G)") (class "Default")
      (node (ref "R1_RM2") (pin "2") (pinfunction "2_2") (pintype "passive"))
      (node (ref "R2_RM2") (pin "1") (pinfunction "1_1") (pintype "passive"))
      (node (ref "RM2_NFET") (pin "1") (pinfunction "G_1") (pintype "passive"))
    )
    (net (code "56") (name "Net-(RM2_NFET1-D)") (class "Default")
      (node (ref "RM2_NFET1") (pin "3") (pinfunction "D_3") (pintype "passive"))
      (node (ref "RM3") (pin "2") (pinfunction "2_2") (pintype "passive"))
    )
    (net (code "57") (name "Net-(RM2_NFET1-G)") (class "Default")
      (node (ref "R1_RM3") (pin "2") (pinfunction "2_2") (pintype "passive"))
      (node (ref "R2_RM3") (pin "1") (pinfunction "1_1") (pintype "passive"))
      (node (ref "RM2_NFET1") (pin "1") (pinfunction "G_1") (pintype "passive"))
    )
    (net (code "58") (name "Net-(RTC-X1)") (class "Default")
      (node (ref "RTC") (pin "1") (pinfunction "X1_1") (pintype "bidirectional"))
      (node (ref "Y1") (pin "X2") (pinfunction "2_X2") (pintype "passive"))
    )
    (net (code "59") (name "Net-(RTC-X2)") (class "Default")
      (node (ref "RTC") (pin "2") (pinfunction "X2_2") (pintype "bidirectional"))
      (node (ref "Y1") (pin "X1") (pinfunction "1_X1") (pintype "passive"))
    )
    (net (code "60") (name "Net-(U$2-A1)") (class "Default")
      (node (ref "A1") (pin "2") (pinfunction "2_2") (pintype "passive"))
      (node (ref "U$2") (pin "2") (pinfunction "A1_2") (pintype "bidirectional"))
    )
    (net (code "61") (name "Net-(U$2-A2)") (class "Default")
      (node (ref "A2") (pin "2") (pinfunction "2_2") (pintype "passive"))
      (node (ref "U$2") (pin "3") (pinfunction "A2_3") (pintype "bidirectional"))
    )
    (net (code "62") (name "Net-(U$3-CHRG)") (class "Default")
      (node (ref "CHRG") (pin "C") (pinfunction "C_C") (pintype "passive"))
      (node (ref "U$3") (pin "1") (pinfunction "CHRG_1") (pintype "bidirectional"))
    )
    (net (code "63") (name "Net-(U$3-PROG)") (class "Default")
      (node (ref "R_PROG_TP4057") (pin "1") (pinfunction "1_1") (pintype "passive"))
      (node (ref "U$3") (pin "6") (pinfunction "PROG_6") (pintype "bidirectional"))
    )
    (net (code "64") (name "Net-(U$3-STDBY)") (class "Default")
      (node (ref "SDBY") (pin "C") (pinfunction "C_C") (pintype "passive"))
      (node (ref "U$3") (pin "5") (pinfunction "STDBY_5") (pintype "bidirectional"))
    )
    (net (code "65") (name "Net-(USB_PWR-PadC)") (class "Default")
      (node (ref "USB_PWR") (pin "C") (pinfunction "C_C") (pintype "passive"))
      (node (ref "USB_PWR_R1") (pin "1") (pinfunction "1_1") (pintype "passive"))
    )
    (net (code "66") (name "PC_RX") (class "Default")
      (node (ref "FT232RL") (pin "1") (pinfunction "TXD_1") (pintype "output"))
      (node (ref "JP2") (pin "3") (pinfunction "TXO_3") (pintype "passive"))
      (node (ref "MKL16") (pin "12") (pinfunction "PTE23_12") (pintype "bidirectional"))
    )
    (net (code "67") (name "PC_TX") (class "Default")
      (node (ref "FT232RL") (pin "5") (pinfunction "RXD_5") (pintype "input"))
      (node (ref "JP2") (pin "2") (pinfunction "RXI_2") (pintype "passive"))
      (node (ref "MKL16") (pin "11") (pinfunction "PTE22_11") (pintype "bidirectional"))
    )
    (net (code "68") (name "RESET") (class "Default")
      (node (ref "JTAG") (pin "15") (pinfunction "RESET_15") (pintype "bidirectional"))
      (node (ref "MKL16") (pin "34") (pinfunction "PTA20_34") (pintype "bidirectional"))
    )
    (net (code "69") (name "RM1") (class "Default")
      (node (ref "MKL16") (pin "55") (pinfunction "PTC10_55") (pintype "bidirectional"))
      (node (ref "R2_RM2") (pin "2") (pinfunction "2_2") (pintype "passive"))
    )
    (net (code "70") (name "RM2") (class "Default")
      (node (ref "MKL16") (pin "56") (pinfunction "PTC11_56") (pintype "bidirectional"))
      (node (ref "R2_RM1") (pin "2") (pinfunction "2_2") (pintype "passive"))
    )
    (net (code "71") (name "RM3") (class "Default")
      (node (ref "MKL16") (pin "54") (pinfunction "PTC9_54") (pintype "bidirectional"))
      (node (ref "R2_RM3") (pin "2") (pinfunction "2_2") (pintype "passive"))
    )
    (net (code "72") (name "RTC_SQW") (class "Default")
      (node (ref "MKL16") (pin "38") (pinfunction "PTB3_38") (pintype "bidirectional"))
      (node (ref "R1_SQW") (pin "1") (pinfunction "1_1") (pintype "passive"))
      (node (ref "RTC") (pin "7") (pinfunction "SQW_7") (pintype "bidirectional"))
    )
    (net (code "73") (name "SWD_CLK") (class "Default")
      (node (ref "JTAG") (pin "9") (pinfunction "TCLK/SWCLK_9") (pintype "bidirectional"))
      (node (ref "MKL16") (pin "22") (pinfunction "PTA0_22") (pintype "bidirectional"))
    )
    (net (code "74") (name "SWD_DIO") (class "Default")
      (node (ref "JTAG") (pin "7") (pinfunction "TMS/SWDIO_7") (pintype "bidirectional"))
      (node (ref "MKL16") (pin "25") (pinfunction "PTA3_25") (pintype "bidirectional"))
    )
    (net (code "75") (name "VBATT") (class "Default")
      (node (ref "BATT") (pin "1") (pinfunction "1_1") (pintype "passive"))
      (node (ref "C1_BD6212") (pin "A") (pinfunction "+_A") (pintype "passive"))
      (node (ref "C1_TP4057") (pin "A") (pinfunction "+_A") (pintype "passive"))
      (node (ref "CAMERA") (pin "1") (pinfunction "1_1") (pintype "passive"))
      (node (ref "H-BRIDGE") (pin "17") (pinfunction "VREF_17") (pintype "passive"))
      (node (ref "H-BRIDGE") (pin "21") (pinfunction "VCC_21") (pintype "power_in"))
      (node (ref "H-BRIDGE") (pin "22") (pinfunction "VCC_22") (pintype "power_in"))
      (node (ref "H-BRIDGE") (pin "23") (pinfunction "VCC_23") (pintype "power_in"))
      (node (ref "JP3") (pin "1") (pinfunction "1_1") (pintype "passive"))
      (node (ref "Q1") (pin "2") (pinfunction "S_2") (pintype "passive"))
      (node (ref "RM1") (pin "1") (pinfunction "1_1") (pintype "passive"))
      (node (ref "RM2") (pin "1") (pinfunction "1_1") (pintype "passive"))
      (node (ref "RM3") (pin "1") (pinfunction "1_1") (pintype "passive"))
      (node (ref "RVD1") (pin "1") (pinfunction "1_1") (pintype "passive"))
      (node (ref "U$3") (pin "3") (pinfunction "BAT_3") (pintype "bidirectional"))
    )
    (net (code "76") (name "VNEG") (class "Default")
      (node (ref "AK8963") (pin "13") (pinfunction "VSS_13") (pintype "power_in"))
      (node (ref "C1_MKL") (pin "2") (pinfunction "2_2") (pintype "passive"))
      (node (ref "C1_MPU6500") (pin "2") (pinfunction "2_2") (pintype "passive"))
      (node (ref "C2_MKL") (pin "2") (pinfunction "2_2") (pintype "passive"))
      (node (ref "C2_MPU6500") (pin "2") (pinfunction "2_2") (pintype "passive"))
      (node (ref "FT232RL") (pin "18") (pinfunction "GND18_18") (pintype "power_in"))
      (node (ref "FT232RL") (pin "21") (pinfunction "GND21_21") (pintype "power_in"))
      (node (ref "FT232RL") (pin "25") (pinfunction "AGND_25") (pintype "power_in"))
      (node (ref "FT232RL") (pin "26") (pinfunction "TEST_26") (pintype "input"))
      (node (ref "FT232RL") (pin "7") (pinfunction "GND7_7") (pintype "power_in"))
      (node (ref "MKL16") (pin "15") (pinfunction "VREFL_15") (pintype "bidirectional"))
      (node (ref "MKL16") (pin "16") (pinfunction "VSSA_16") (pintype "bidirectional"))
      (node (ref "MKL16") (pin "31") (pinfunction "VSS2_31") (pintype "bidirectional"))
      (node (ref "MKL16") (pin "4") (pinfunction "VSS_4") (pintype "bidirectional"))
      (node (ref "MKL16") (pin "47") (pinfunction "VSS3_47") (pintype "bidirectional"))
      (node (ref "MPU-6500") (pin "11") (pinfunction "FSYNC_11") (pintype "bidirectional"))
      (node (ref "MPU-6500") (pin "18") (pinfunction "GND_18") (pintype "bidirectional"))
      (node (ref "MPU-6500") (pin "20") (pinfunction "RESV-GND_20") (pintype "bidirectional"))
      (node (ref "PT1") (pin "P$1") (pinfunction "P$1_P$1") (pintype "bidirectional"))
      (node (ref "R_AUXJUMP") (pin "1") (pinfunction "1_1") (pintype "passive"))
      (node (ref "R_AUXJUMP1") (pin "1") (pinfunction "1_1") (pintype "passive"))
      (node (ref "R_AUXJUMP2") (pin "1") (pinfunction "1_1") (pintype "passive"))
    )
    (net (code "77") (name "VREF_1.25V") (class "Default")
      (node (ref "C1_VREF") (pin "2") (pinfunction "2_2") (pintype "passive"))
      (node (ref "MKL16") (pin "14") (pinfunction "VREFH_14") (pintype "bidirectional"))
      (node (ref "R1_SHUNT") (pin "1") (pinfunction "1_1") (pintype "passive"))
      (node (ref "U$5") (pin "8") (pinfunction "VIN_8") (pintype "bidirectional"))
    )
    (net (code "78") (name "VREGIN") (class "Default")
      (node (ref "BATT_PWR") (pin "A") (pinfunction "A_A") (pintype "passive"))
      (node (ref "C2") (pin "1") (pinfunction "1_1") (pintype "passive"))
      (node (ref "Q1") (pin "3") (pinfunction "D_3") (pintype "passive"))
      (node (ref "U$7") (pin "1") (pinfunction "IN_1") (pintype "input"))
    )
    (net (code "79") (name "VSENSE") (class "Default")
      (node (ref "MKL16") (pin "37") (pinfunction "PTB2_37") (pintype "bidirectional"))
      (node (ref "RVD1") (pin "2") (pinfunction "2_2") (pintype "passive"))
      (node (ref "RVD2") (pin "1") (pinfunction "1_1") (pintype "passive"))
    )
    (net (code "80") (name "VSENSE2") (class "Default")
      (node (ref "MKL16") (pin "19") (pinfunction "PTE31_19") (pintype "bidirectional"))
      (node (ref "RVD3") (pin "2") (pinfunction "2_2") (pintype "passive"))
      (node (ref "RVD4") (pin "1") (pinfunction "1_1") (pintype "passive"))
    )
    (net (code "81") (name "XBEE_DTR") (class "Default")
      (node (ref "XBEE") (pin "9") (pinfunction "DTR/DI8_9") (pintype "input"))
    )
    (net (code "82") (name "XBEE_RTS") (class "Default")
      (node (ref "XBEE") (pin "16") (pinfunction "RTS/AD6/DIO6_16") (pintype "bidirectional"))
    )
    (net (code "83") (name "XTAL1") (class "Default")
      (node (ref "C3_OSC1") (pin "2") (pinfunction "2_2") (pintype "passive"))
      (node (ref "MKL16") (pin "33") (pinfunction "PTA19_33") (pintype "bidirectional"))
      (node (ref "R2_OSC") (pin "2") (pinfunction "2_2") (pintype "passive"))
      (node (ref "Y2") (pin "3") (pinfunction "2_3") (pintype "passive"))
    )
    (net (code "84") (name "XTAL2") (class "Default")
      (node (ref "C4_OSC1") (pin "2") (pinfunction "2_2") (pintype "passive"))
      (node (ref "MKL16") (pin "32") (pinfunction "PTA18_32") (pintype "bidirectional"))
      (node (ref "R2_OSC") (pin "1") (pinfunction "1_1") (pintype "passive"))
      (node (ref "Y2") (pin "1") (pinfunction "1_1") (pintype "passive"))
    )
    (net (code "85") (name "unconnected-(AK8963-DRDY-Pad1)") (class "Default")
      (node (ref "AK8963") (pin "1") (pinfunction "DRDY_1") (pintype "input"))
    )
    (net (code "86") (name "unconnected-(AK8963-SO-Pad6)") (class "Default")
      (node (ref "AK8963") (pin "6") (pinfunction "SO_6") (pintype "output"))
    )
    (net (code "87") (name "unconnected-(AK8963-TRG-Pad7)") (class "Default")
      (node (ref "AK8963") (pin "7") (pinfunction "TRG_7") (pintype "input"))
    )
    (net (code "88") (name "unconnected-(FT232RL-CTS-Pad11)") (class "Default")
      (node (ref "FT232RL") (pin "11") (pinfunction "CTS_11") (pintype "input"))
    )
    (net (code "89") (name "unconnected-(FT232RL-DCD-Pad10)") (class "Default")
      (node (ref "FT232RL") (pin "10") (pinfunction "DCD_10") (pintype "input"))
    )
    (net (code "90") (name "unconnected-(FT232RL-DSR-Pad9)") (class "Default")
      (node (ref "FT232RL") (pin "9") (pinfunction "DSR_9") (pintype "input"))
    )
    (net (code "91") (name "unconnected-(FT232RL-DTR-Pad2)") (class "Default")
      (node (ref "FT232RL") (pin "2") (pinfunction "DTR_2") (pintype "output"))
    )
    (net (code "92") (name "unconnected-(FT232RL-OSCI-Pad27)") (class "Default")
      (node (ref "FT232RL") (pin "27") (pinfunction "OSCI_27") (pintype "input"))
    )
    (net (code "93") (name "unconnected-(FT232RL-OSCO-Pad28)") (class "Default")
      (node (ref "FT232RL") (pin "28") (pinfunction "OSCO_28") (pintype "output"))
    )
    (net (code "94") (name "unconnected-(FT232RL-PWREN-Pad14)") (class "Default")
      (node (ref "FT232RL") (pin "14") (pinfunction "PWREN_14") (pintype "input"))
    )
    (net (code "95") (name "unconnected-(FT232RL-RESET-Pad19)") (class "Default")
      (node (ref "FT232RL") (pin "19") (pinfunction "RESET_19") (pintype "input"))
    )
    (net (code "96") (name "unconnected-(FT232RL-RI-Pad6)") (class "Default")
      (node (ref "FT232RL") (pin "6") (pinfunction "RI_6") (pintype "input"))
    )
    (net (code "97") (name "unconnected-(FT232RL-RTS-Pad3)") (class "Default")
      (node (ref "FT232RL") (pin "3") (pinfunction "RTS_3") (pintype "output"))
    )
    (net (code "98") (name "unconnected-(FT232RL-SLEEP-Pad12)") (class "Default")
      (node (ref "FT232RL") (pin "12") (pinfunction "SLEEP_12") (pintype "input"))
    )
    (net (code "99") (name "unconnected-(FT232RL-TXDEN-Pad13)") (class "Default")
      (node (ref "FT232RL") (pin "13") (pinfunction "TXDEN_13") (pintype "input"))
    )
    (net (code "100") (name "unconnected-(JP2-CTS-Pad5)") (class "Default")
      (node (ref "JP2") (pin "5") (pinfunction "CTS_5") (pintype "passive"))
    )
    (net (code "101") (name "unconnected-(JP2-DTR-Pad1)") (class "Default")
      (node (ref "JP2") (pin "1") (pinfunction "DTR_1") (pintype "passive"))
    )
    (net (code "102") (name "unconnected-(JTAG-NC-Pad17)") (class "Default")
      (node (ref "JTAG") (pin "17") (pinfunction "NC_17") (pintype "bidirectional"))
    )
    (net (code "103") (name "unconnected-(JTAG-NC2-Pad19)") (class "Default")
      (node (ref "JTAG") (pin "19") (pinfunction "NC2_19") (pintype "bidirectional"))
    )
    (net (code "104") (name "unconnected-(JTAG-RTCK\\-Pad11)") (class "Default")
      (node (ref "JTAG") (pin "11") (pinfunction "RTCK\\_11") (pintype "bidirectional"))
    )
    (net (code "105") (name "unconnected-(JTAG-TDI-Pad5)") (class "Default")
      (node (ref "JTAG") (pin "5") (pinfunction "TDI_5") (pintype "bidirectional"))
    )
    (net (code "106") (name "unconnected-(JTAG-TDO{slash}SWO-Pad13)") (class "Default")
      (node (ref "JTAG") (pin "13") (pinfunction "TDO/SWO_13") (pintype "bidirectional"))
    )
    (net (code "107") (name "unconnected-(JTAG-TRST\\-Pad3)") (class "Default")
      (node (ref "JTAG") (pin "3") (pinfunction "TRST\\_3") (pintype "bidirectional"))
    )
    (net (code "108") (name "unconnected-(MKL16-PTB16-Pad39)") (class "Default")
      (node (ref "MKL16") (pin "39") (pinfunction "PTB16_39") (pintype "bidirectional"))
    )
    (net (code "109") (name "unconnected-(MKL16-PTB17-Pad40)") (class "Default")
      (node (ref "MKL16") (pin "40") (pinfunction "PTB17_40") (pintype "bidirectional"))
    )
    (net (code "110") (name "unconnected-(MKL16-PTB18-Pad41)") (class "Default")
      (node (ref "MKL16") (pin "41") (pinfunction "PTB18_41") (pintype "bidirectional"))
    )
    (net (code "111") (name "unconnected-(MKL16-PTB19-Pad42)") (class "Default")
      (node (ref "MKL16") (pin "42") (pinfunction "PTB19_42") (pintype "bidirectional"))
    )
    (net (code "112") (name "unconnected-(MKL16-PTC1{slash}LLWU_P6{slash}RTC_CLKIN-Pad44)") (class "Default")
      (node (ref "MKL16") (pin "44") (pinfunction "PTC1/LLWU_P6/RTC_CLKIN_44") (pintype "bidirectional"))
    )
    (net (code "113") (name "unconnected-(MKL16-PTC2-Pad45)") (class "Default")
      (node (ref "MKL16") (pin "45") (pinfunction "PTC2_45") (pintype "bidirectional"))
    )
    (net (code "114") (name "unconnected-(MKL16-PTC3{slash}LLWU_P7-Pad46)") (class "Default")
      (node (ref "MKL16") (pin "46") (pinfunction "PTC3/LLWU_P7_46") (pintype "bidirectional"))
    )
    (net (code "115") (name "unconnected-(MKL16-PTC4{slash}LLWU_P8-Pad49)") (class "Default")
      (node (ref "MKL16") (pin "49") (pinfunction "PTC4/LLWU_P8_49") (pintype "bidirectional"))
    )
    (net (code "116") (name "unconnected-(MKL16-PTC6{slash}LLWU_P10-Pad51)") (class "Default")
      (node (ref "MKL16") (pin "51") (pinfunction "PTC6/LLWU_P10_51") (pintype "bidirectional"))
    )
    (net (code "117") (name "unconnected-(MKL16-PTC7-Pad52)") (class "Default")
      (node (ref "MKL16") (pin "52") (pinfunction "PTC7_52") (pintype "bidirectional"))
    )
    (net (code "118") (name "unconnected-(MKL16-PTC8-Pad53)") (class "Default")
      (node (ref "MKL16") (pin "53") (pinfunction "PTC8_53") (pintype "bidirectional"))
    )
    (net (code "119") (name "unconnected-(MKL16-PTD5-Pad62)") (class "Default")
      (node (ref "MKL16") (pin "62") (pinfunction "PTD5_62") (pintype "bidirectional"))
    )
    (net (code "120") (name "unconnected-(MKL16-PTD6{slash}LLWU_P15-Pad63)") (class "Default")
      (node (ref "MKL16") (pin "63") (pinfunction "PTD6/LLWU_P15_63") (pintype "bidirectional"))
    )
    (net (code "121") (name "unconnected-(MKL16-PTD7-Pad64)") (class "Default")
      (node (ref "MKL16") (pin "64") (pinfunction "PTD7_64") (pintype "bidirectional"))
    )
    (net (code "122") (name "unconnected-(MKL16-PTE16-Pad5)") (class "Default")
      (node (ref "MKL16") (pin "5") (pinfunction "PTE16_5") (pintype "bidirectional"))
    )
    (net (code "123") (name "unconnected-(MKL16-PTE17-Pad6)") (class "Default")
      (node (ref "MKL16") (pin "6") (pinfunction "PTE17_6") (pintype "bidirectional"))
    )
    (net (code "124") (name "unconnected-(MKL16-PTE18-Pad7)") (class "Default")
      (node (ref "MKL16") (pin "7") (pinfunction "PTE18_7") (pintype "bidirectional"))
    )
    (net (code "125") (name "unconnected-(MKL16-PTE19-Pad8)") (class "Default")
      (node (ref "MKL16") (pin "8") (pinfunction "PTE19_8") (pintype "bidirectional"))
    )
    (net (code "126") (name "unconnected-(MKL16-PTE29-Pad17)") (class "Default")
      (node (ref "MKL16") (pin "17") (pinfunction "PTE29_17") (pintype "bidirectional"))
    )
    (net (code "127") (name "unconnected-(MKL16-TC5{slash}LLWU_P9-Pad50)") (class "Default")
      (node (ref "MKL16") (pin "50") (pinfunction "TC5/LLWU_P9_50") (pintype "bidirectional"))
    )
    (net (code "128") (name "unconnected-(MPU-6500-~{CS}-Pad22)") (class "Default")
      (node (ref "MPU-6500") (pin "22") (pinfunction "~{CS}_22") (pintype "bidirectional"))
    )
    (net (code "129") (name "unconnected-(U$2-NC-Pad1)") (class "Default")
      (node (ref "U$2") (pin "1") (pinfunction "NC_1") (pintype "no_connect"))
    )
    (net (code "130") (name "unconnected-(XBEE-AD0{slash}DIO0-Pad20)") (class "Default")
      (node (ref "XBEE") (pin "20") (pinfunction "AD0/DIO0_20") (pintype "bidirectional"))
    )
    (net (code "131") (name "unconnected-(XBEE-AD1{slash}DIO1-Pad19)") (class "Default")
      (node (ref "XBEE") (pin "19") (pinfunction "AD1/DIO1_19") (pintype "bidirectional"))
    )
    (net (code "132") (name "unconnected-(XBEE-AD2{slash}DIO2-Pad18)") (class "Default")
      (node (ref "XBEE") (pin "18") (pinfunction "AD2/DIO2_18") (pintype "bidirectional"))
    )
    (net (code "133") (name "unconnected-(XBEE-AD3{slash}DIO3-Pad17)") (class "Default")
      (node (ref "XBEE") (pin "17") (pinfunction "AD3/DIO3_17") (pintype "bidirectional"))
    )
    (net (code "134") (name "unconnected-(XBEE-AD4{slash}DIO4-Pad11)") (class "Default")
      (node (ref "XBEE") (pin "11") (pinfunction "AD4/DIO4_11") (pintype "bidirectional"))
    )
    (net (code "135") (name "unconnected-(XBEE-ASC{slash}AD5{slash}DIO5-Pad15)") (class "Default")
      (node (ref "XBEE") (pin "15") (pinfunction "ASC/AD5/DIO5_15") (pintype "bidirectional"))
    )
    (net (code "136") (name "unconnected-(XBEE-CTS{slash}DIO7-Pad12)") (class "Default")
      (node (ref "XBEE") (pin "12") (pinfunction "CTS/DIO7_12") (pintype "bidirectional"))
    )
    (net (code "137") (name "unconnected-(XBEE-DO8-Pad4)") (class "Default")
      (node (ref "XBEE") (pin "4") (pinfunction "DO8_4") (pintype "output"))
    )
    (net (code "138") (name "unconnected-(XBEE-ON{slash}SLEEP-Pad13)") (class "Default")
      (node (ref "XBEE") (pin "13") (pinfunction "ON/SLEEP_13") (pintype "output"))
    )
    (net (code "139") (name "unconnected-(XBEE-PWM0{slash}RSSI-Pad6)") (class "Default")
      (node (ref "XBEE") (pin "6") (pinfunction "PWM0/RSSI_6") (pintype "output"))
    )
    (net (code "140") (name "unconnected-(XBEE-PWM1-Pad7)") (class "Default")
      (node (ref "XBEE") (pin "7") (pinfunction "PWM1_7") (pintype "output"))
    )
    (net (code "141") (name "unconnected-(XBEE-RESERVED-Pad8)") (class "Default")
      (node (ref "XBEE") (pin "8") (pinfunction "RESERVED_8") (pintype "no_connect"))
    )
    (net (code "142") (name "unconnected-(XBEE-RESET-Pad5)") (class "Default")
      (node (ref "XBEE") (pin "5") (pinfunction "RESET_5") (pintype "input"))
    )
  )
)
